# Tiva_Xbee.net
KiCad netlist of a schematic drawn in EAGLE
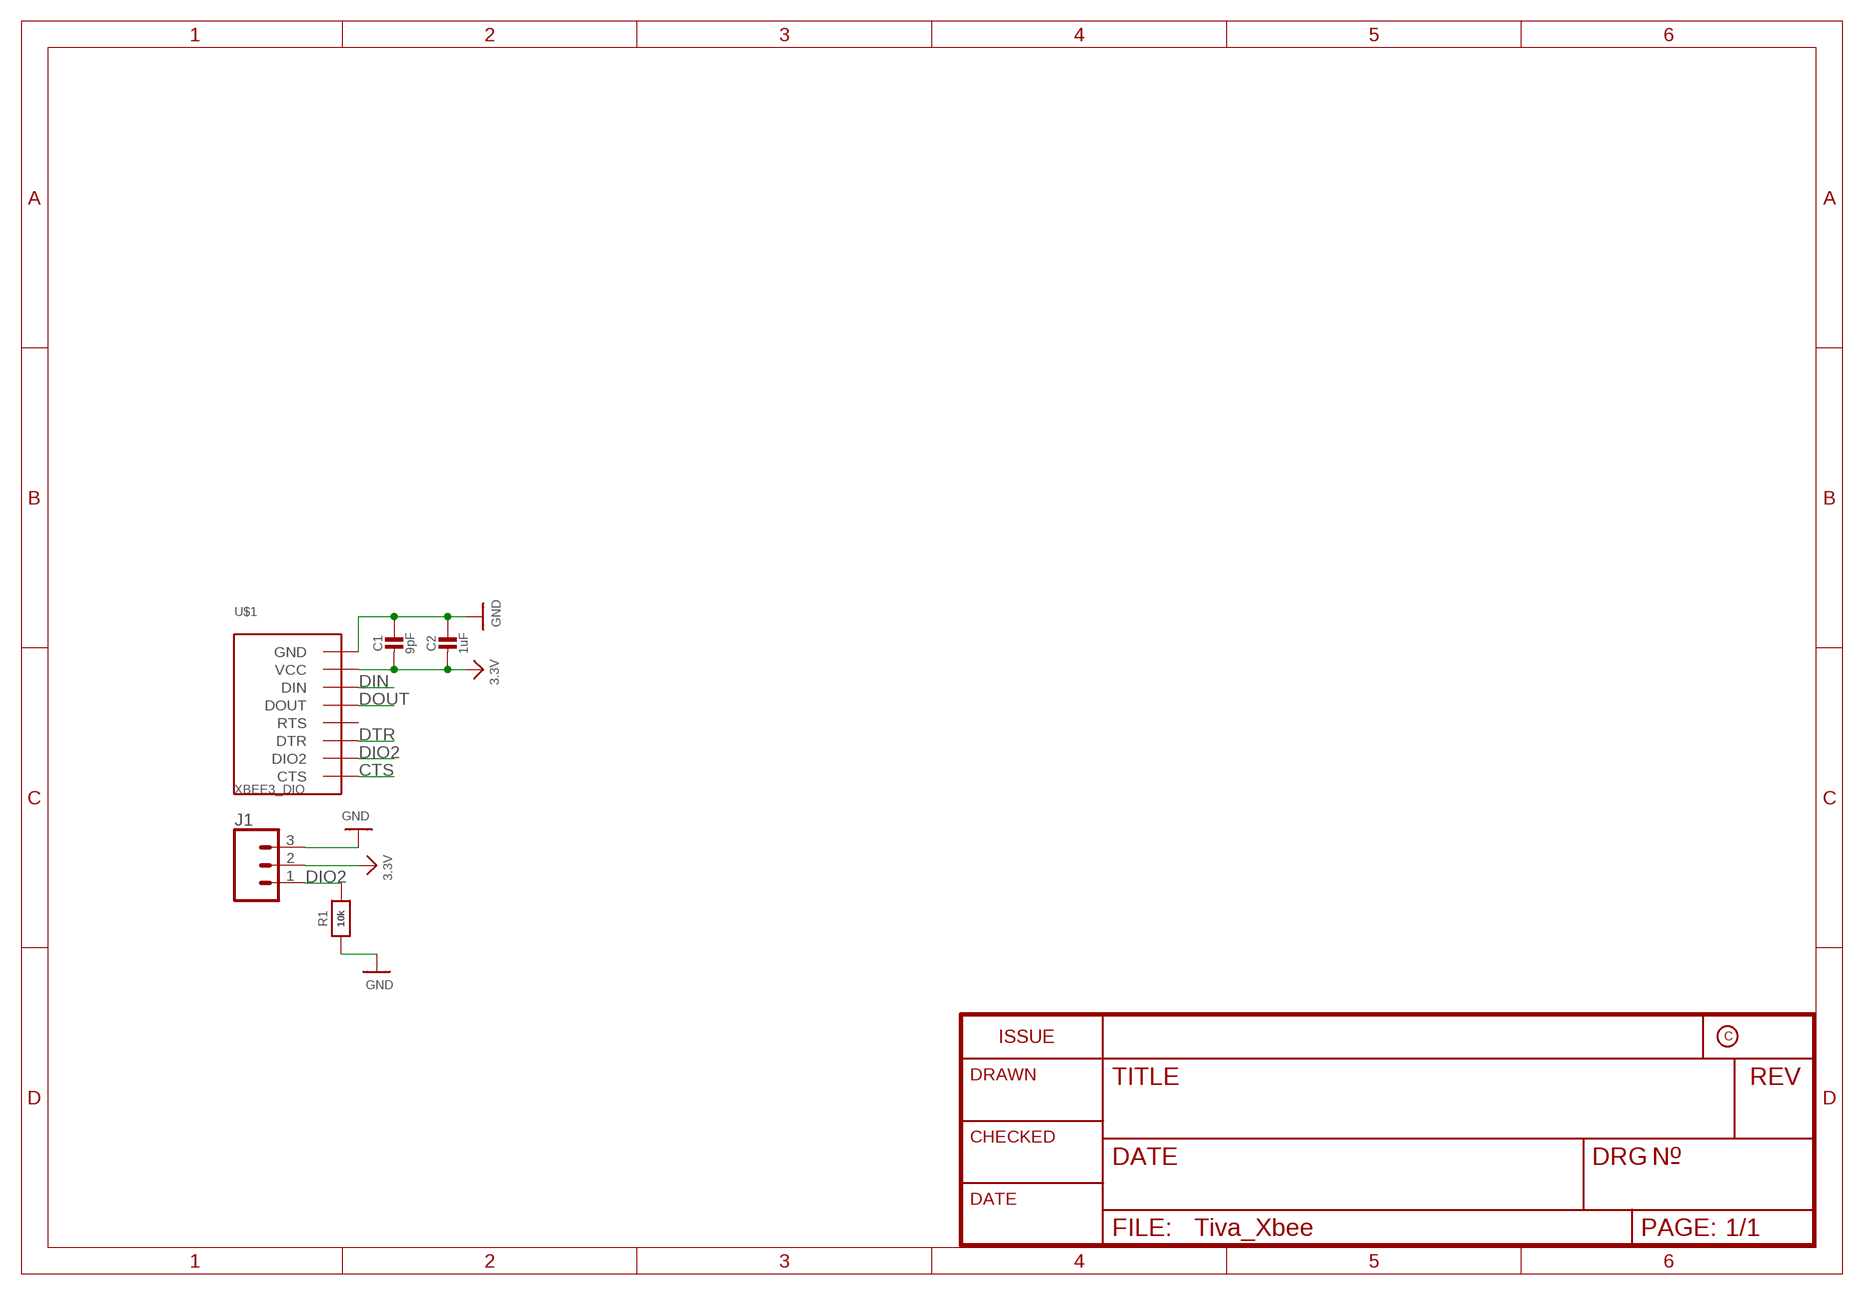
[diagram p0: schematic, sheet 1]

(export (version "E")
  (design (tool "Eeschema 10.0.6"))
  (components
    (comp (ref "C1")
      (value "9pF")
      (footprint "eagle-import:_0603")
      (libsource (lib "eagle-import") (part "CAP_CERAMIC_0603"))
    )
    (comp (ref "C2")
      (value "1uF")
      (footprint "eagle-import:_0603")
      (libsource (lib "eagle-import") (part "CAP_CERAMIC_0603"))
    )
    (comp (ref "J1")
      (value "CONN_03")
      (footprint "eagle-import:1X03")
      (libsource (lib "eagle-import") (part "CONN_03"))
    )
    (comp (ref "R1")
      (value "10k")
      (footprint "eagle-import:_0603")
      (libsource (lib "eagle-import") (part "RESISTOR_0603"))
    )
    (comp (ref "U$1")
      (value "XBEE3_DIO")
      (footprint "eagle-import:XBEE3_MICRO")
      (libsource (lib "eagle-import") (part "XBEE3_DIO"))
    )
  )
  (nets
    (net (code "1") (name "/CTS") (class "Default")
      (node (ref "U$1") (pin "CTS/DIO7") (pinfunction "CTS_CTS/DIO7") (pintype "bidirectional"))
    )
    (net (code "2") (name "/DIN") (class "Default")
      (node (ref "U$1") (pin "DIN/CONFIG/DIO14") (pinfunction "DIN_DIN/CONFIG/DIO14") (pintype "bidirectional"))
    )
    (net (code "3") (name "/DIO2") (class "Default")
      (node (ref "J1") (pin "1") (pinfunction "1_1") (pintype "passive"))
      (node (ref "R1") (pin "2") (pinfunction "2_2") (pintype "passive"))
      (node (ref "U$1") (pin "AD2/DIO2") (pinfunction "DIO2_AD2/DIO2") (pintype "bidirectional"))
    )
    (net (code "4") (name "/DOUT") (class "Default")
      (node (ref "U$1") (pin "DOUT/DIO13") (pinfunction "DOUT_DOUT/DIO13") (pintype "bidirectional"))
    )
    (net (code "5") (name "/DTR") (class "Default")
      (node (ref "U$1") (pin "DTR/SLEEP_RQ/DIO8") (pinfunction "DTR_DTR/SLEEP_RQ/DIO8") (pintype "bidirectional"))
    )
    (net (code "6") (name "3.3V") (class "Default")
      (node (ref "C1") (pin "2") (pinfunction "2_2") (pintype "passive"))
      (node (ref "C2") (pin "2") (pinfunction "2_2") (pintype "passive"))
      (node (ref "J1") (pin "2") (pinfunction "2_2") (pintype "passive"))
      (node (ref "U$1") (pin "VCC") (pinfunction "VCC_VCC") (pintype "bidirectional"))
    )
    (net (code "7") (name "GND") (class "Default")
      (node (ref "C1") (pin "1") (pinfunction "1_1") (pintype "passive"))
      (node (ref "C2") (pin "1") (pinfunction "1_1") (pintype "passive"))
      (node (ref "J1") (pin "3") (pinfunction "3_3") (pintype "passive"))
      (node (ref "R1") (pin "1") (pinfunction "1_1") (pintype "passive"))
      (node (ref "U$1") (pin "GND1") (pinfunction "GND_GND1") (pintype "bidirectional"))
      (node (ref "U$1") (pin "GND2") (pinfunction "GND_GND2") (pintype "bidirectional"))
      (node (ref "U$1") (pin "GND3") (pinfunction "GND_GND3") (pintype "bidirectional"))
      (node (ref "U$1") (pin "GND4") (pinfunction "GND_GND4") (pintype "bidirectional"))
      (node (ref "U$1") (pin "GND5") (pinfunction "GND_GND5") (pintype "bidirectional"))
      (node (ref "U$1") (pin "GND6") (pinfunction "GND_GND6") (pintype "bidirectional"))
    )
    (net (code "8") (name "unconnected-(U$1-RTS-PadRTS{slash}DIO6)") (class "Default")
      (node (ref "U$1") (pin "RTS/DIO6") (pinfunction "RTS_RTS/DIO6") (pintype "bidirectional"))
    )
  )
)
